# SolarPanel1.net
KiCad netlist of a schematic drawn in Altium Designer
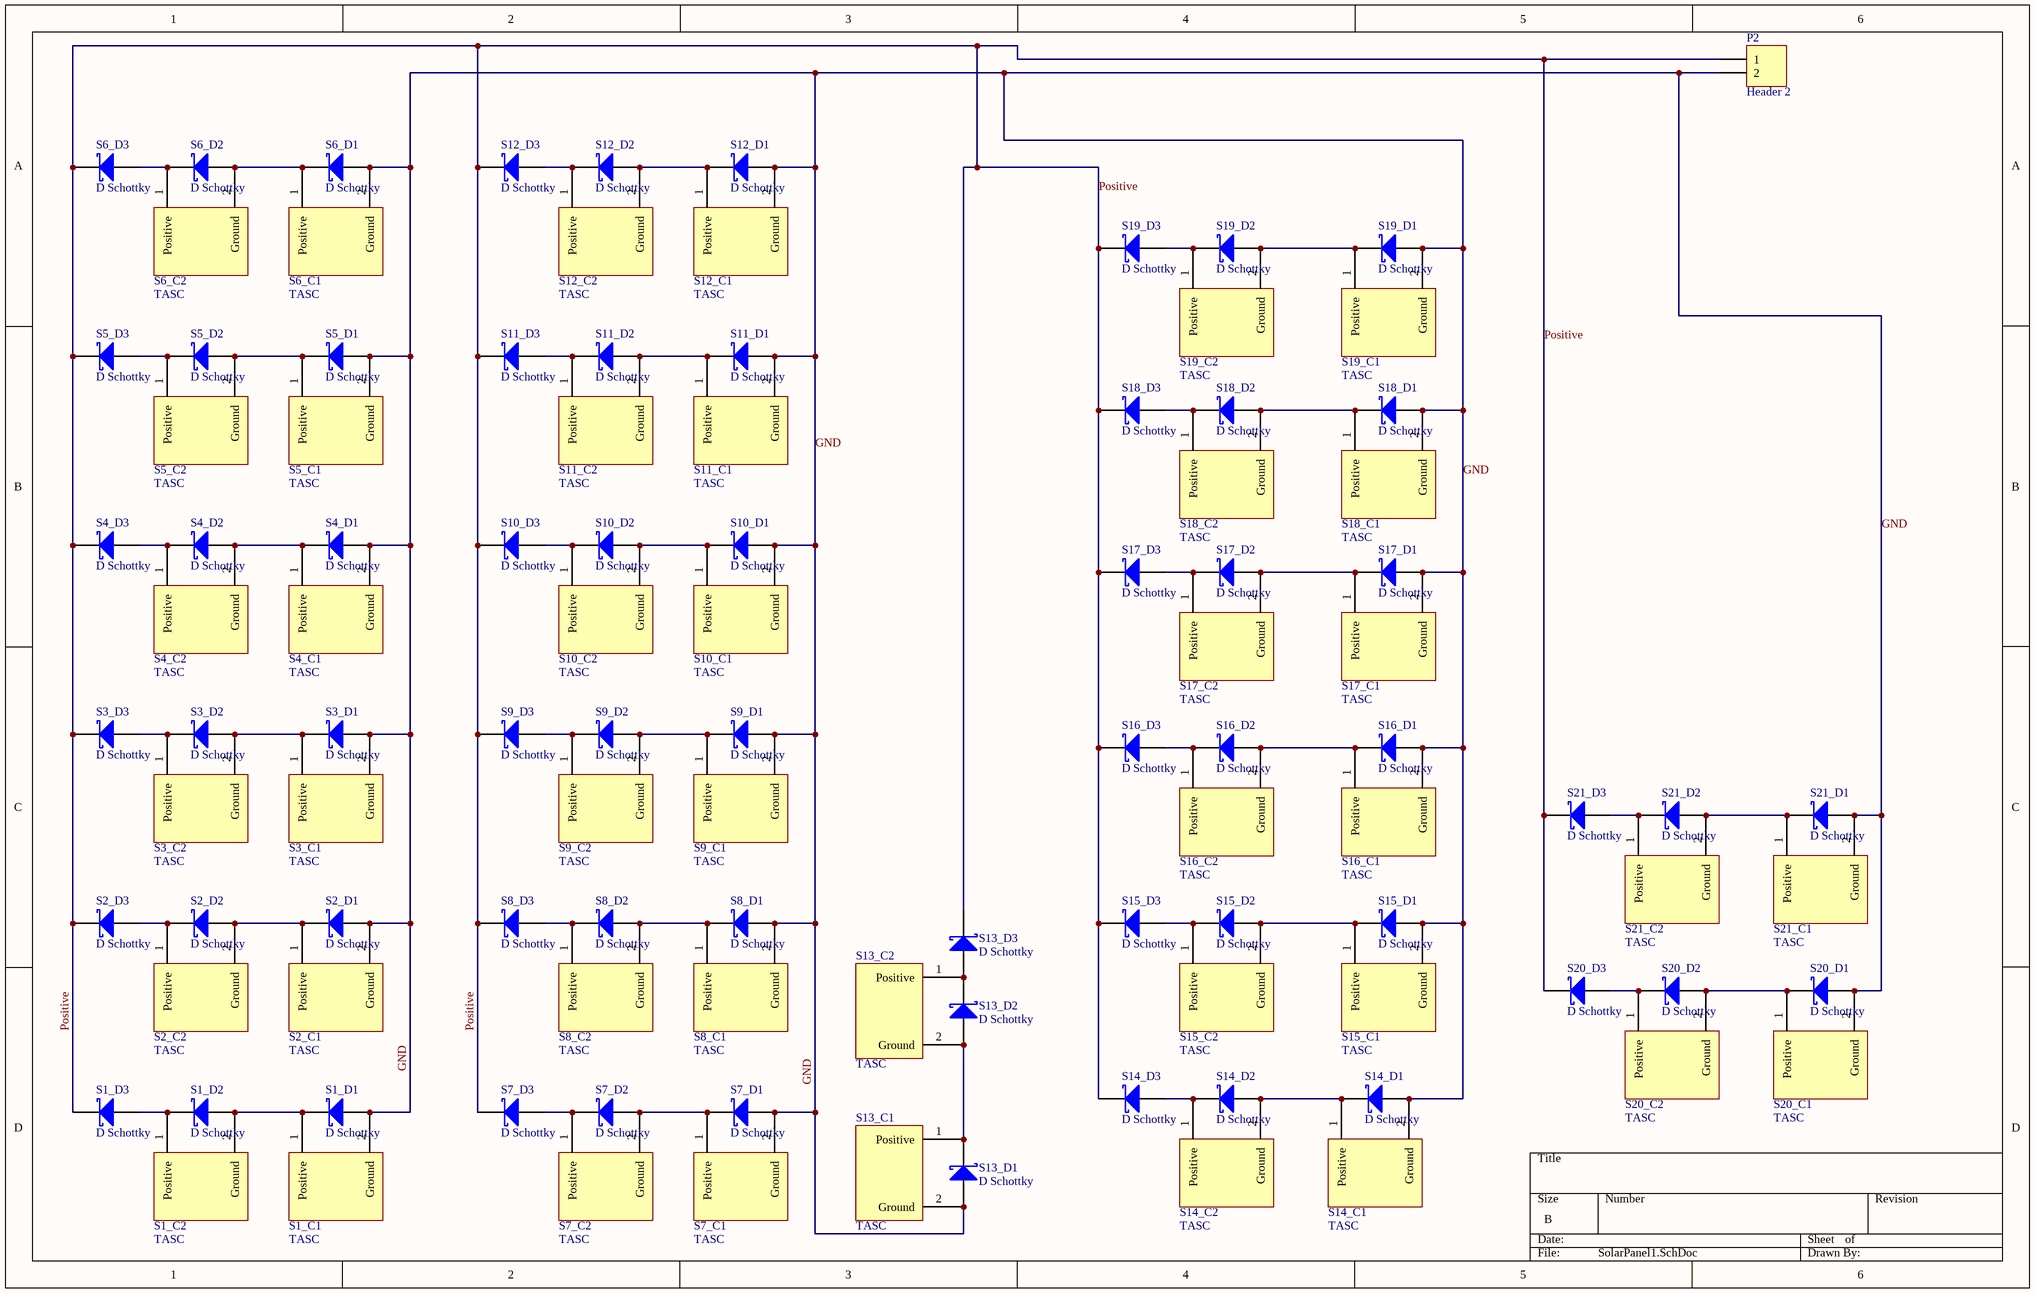
[diagram p0: SolarPanel1.SchDoc]

(export (version "E")
  (design (tool "Eeschema 10.0.6"))
  (components
    (comp (ref "P2")
      (value "Header 2")
      (footprint "HDR1X2")
      (description "Header, 2-Pin")
      (fields (field (name "PUBLISHER") "Altium Limited"))
      (libsource (lib "Miscellaneous Connectors") (part "Header 2"))
    )
    (comp (ref "S1_C1")
      (value "TASC")
      (footprint "PCBComponent_1")
      (description "TASC Solar Cell")
      (libsource (lib "SolarPanel1") (part "TASC"))
    )
    (comp (ref "S1_C2")
      (value "TASC")
      (footprint "PCBComponent_1")
      (description "TASC Solar Cell")
      (libsource (lib "SolarPanel1") (part "TASC"))
    )
    (comp (ref "S1_D1")
      (value "D Schottky")
      (footprint "SMB")
      (description "Schottky Diode")
      (fields (field (name "PUBLISHER") "Altium Limited"))
      (libsource (lib "Miscellaneous Devices") (part "D Schottky"))
    )
    (comp (ref "S1_D2")
      (value "D Schottky")
      (footprint "SMB")
      (description "Schottky Diode")
      (fields (field (name "PUBLISHER") "Altium Limited"))
      (libsource (lib "Miscellaneous Devices") (part "D Schottky"))
    )
    (comp (ref "S1_D3")
      (value "D Schottky")
      (footprint "SMB")
      (description "Schottky Diode")
      (fields (field (name "PUBLISHER") "Altium Limited"))
      (libsource (lib "Miscellaneous Devices") (part "D Schottky"))
    )
    (comp (ref "S2_C1")
      (value "TASC")
      (footprint "PCBComponent_1")
      (description "TASC Solar Cell")
      (libsource (lib "SolarPanel1") (part "TASC"))
    )
    (comp (ref "S2_C2")
      (value "TASC")
      (footprint "PCBComponent_1")
      (description "TASC Solar Cell")
      (libsource (lib "SolarPanel1") (part "TASC"))
    )
    (comp (ref "S2_D1")
      (value "D Schottky")
      (footprint "SMB")
      (description "Schottky Diode")
      (fields (field (name "PUBLISHER") "Altium Limited"))
      (libsource (lib "Miscellaneous Devices") (part "D Schottky"))
    )
    (comp (ref "S2_D2")
      (value "D Schottky")
      (footprint "SMB")
      (description "Schottky Diode")
      (fields (field (name "PUBLISHER") "Altium Limited"))
      (libsource (lib "Miscellaneous Devices") (part "D Schottky"))
    )
    (comp (ref "S2_D3")
      (value "D Schottky")
      (footprint "SMB")
      (description "Schottky Diode")
      (fields (field (name "PUBLISHER") "Altium Limited"))
      (libsource (lib "Miscellaneous Devices") (part "D Schottky"))
    )
    (comp (ref "S3_C1")
      (value "TASC")
      (footprint "PCBComponent_1")
      (description "TASC Solar Cell")
      (libsource (lib "SolarPanel1") (part "TASC"))
    )
    (comp (ref "S3_C2")
      (value "TASC")
      (footprint "PCBComponent_1")
      (description "TASC Solar Cell")
      (libsource (lib "SolarPanel1") (part "TASC"))
    )
    (comp (ref "S3_D1")
      (value "D Schottky")
      (footprint "SMB")
      (description "Schottky Diode")
      (fields (field (name "PUBLISHER") "Altium Limited"))
      (libsource (lib "Miscellaneous Devices") (part "D Schottky"))
    )
    (comp (ref "S3_D2")
      (value "D Schottky")
      (footprint "SMB")
      (description "Schottky Diode")
      (fields (field (name "PUBLISHER") "Altium Limited"))
      (libsource (lib "Miscellaneous Devices") (part "D Schottky"))
    )
    (comp (ref "S3_D3")
      (value "D Schottky")
      (footprint "SMB")
      (description "Schottky Diode")
      (fields (field (name "PUBLISHER") "Altium Limited"))
      (libsource (lib "Miscellaneous Devices") (part "D Schottky"))
    )
    (comp (ref "S4_C1")
      (value "TASC")
      (footprint "PCBComponent_1")
      (description "TASC Solar Cell")
      (libsource (lib "SolarPanel1") (part "TASC"))
    )
    (comp (ref "S4_C2")
      (value "TASC")
      (footprint "PCBComponent_1")
      (description "TASC Solar Cell")
      (libsource (lib "SolarPanel1") (part "TASC"))
    )
    (comp (ref "S4_D1")
      (value "D Schottky")
      (footprint "SMB")
      (description "Schottky Diode")
      (fields (field (name "PUBLISHER") "Altium Limited"))
      (libsource (lib "Miscellaneous Devices") (part "D Schottky"))
    )
    (comp (ref "S4_D2")
      (value "D Schottky")
      (footprint "SMB")
      (description "Schottky Diode")
      (fields (field (name "PUBLISHER") "Altium Limited"))
      (libsource (lib "Miscellaneous Devices") (part "D Schottky"))
    )
    (comp (ref "S4_D3")
      (value "D Schottky")
      (footprint "SMB")
      (description "Schottky Diode")
      (fields (field (name "PUBLISHER") "Altium Limited"))
      (libsource (lib "Miscellaneous Devices") (part "D Schottky"))
    )
    (comp (ref "S5_C1")
      (value "TASC")
      (footprint "PCBComponent_1")
      (description "TASC Solar Cell")
      (libsource (lib "SolarPanel1") (part "TASC"))
    )
    (comp (ref "S5_C2")
      (value "TASC")
      (footprint "PCBComponent_1")
      (description "TASC Solar Cell")
      (libsource (lib "SolarPanel1") (part "TASC"))
    )
    (comp (ref "S5_D1")
      (value "D Schottky")
      (footprint "SMB")
      (description "Schottky Diode")
      (fields (field (name "PUBLISHER") "Altium Limited"))
      (libsource (lib "Miscellaneous Devices") (part "D Schottky"))
    )
    (comp (ref "S5_D2")
      (value "D Schottky")
      (footprint "SMB")
      (description "Schottky Diode")
      (fields (field (name "PUBLISHER") "Altium Limited"))
      (libsource (lib "Miscellaneous Devices") (part "D Schottky"))
    )
    (comp (ref "S5_D3")
      (value "D Schottky")
      (footprint "SMB")
      (description "Schottky Diode")
      (fields (field (name "PUBLISHER") "Altium Limited"))
      (libsource (lib "Miscellaneous Devices") (part "D Schottky"))
    )
    (comp (ref "S6_C1")
      (value "TASC")
      (footprint "PCBComponent_1")
      (description "TASC Solar Cell")
      (libsource (lib "SolarPanel1") (part "TASC"))
    )
    (comp (ref "S6_C2")
      (value "TASC")
      (footprint "PCBComponent_1")
      (description "TASC Solar Cell")
      (libsource (lib "SolarPanel1") (part "TASC"))
    )
    (comp (ref "S6_D1")
      (value "D Schottky")
      (footprint "SMB")
      (description "Schottky Diode")
      (fields (field (name "PUBLISHER") "Altium Limited"))
      (libsource (lib "Miscellaneous Devices") (part "D Schottky"))
    )
    (comp (ref "S6_D2")
      (value "D Schottky")
      (footprint "SMB")
      (description "Schottky Diode")
      (fields (field (name "PUBLISHER") "Altium Limited"))
      (libsource (lib "Miscellaneous Devices") (part "D Schottky"))
    )
    (comp (ref "S6_D3")
      (value "D Schottky")
      (footprint "SMB")
      (description "Schottky Diode")
      (fields (field (name "PUBLISHER") "Altium Limited"))
      (libsource (lib "Miscellaneous Devices") (part "D Schottky"))
    )
    (comp (ref "S7_C1")
      (value "TASC")
      (footprint "PCBComponent_1")
      (description "TASC Solar Cell")
      (libsource (lib "SolarPanel1") (part "TASC"))
    )
    (comp (ref "S7_C2")
      (value "TASC")
      (footprint "PCBComponent_1")
      (description "TASC Solar Cell")
      (libsource (lib "SolarPanel1") (part "TASC"))
    )
    (comp (ref "S7_D1")
      (value "D Schottky")
      (footprint "SMB")
      (description "Schottky Diode")
      (fields (field (name "PUBLISHER") "Altium Limited"))
      (libsource (lib "Miscellaneous Devices") (part "D Schottky"))
    )
    (comp (ref "S7_D2")
      (value "D Schottky")
      (footprint "SMB")
      (description "Schottky Diode")
      (fields (field (name "PUBLISHER") "Altium Limited"))
      (libsource (lib "Miscellaneous Devices") (part "D Schottky"))
    )
    (comp (ref "S7_D3")
      (value "D Schottky")
      (footprint "SMB")
      (description "Schottky Diode")
      (fields (field (name "PUBLISHER") "Altium Limited"))
      (libsource (lib "Miscellaneous Devices") (part "D Schottky"))
    )
    (comp (ref "S8_C1")
      (value "TASC")
      (footprint "PCBComponent_1")
      (description "TASC Solar Cell")
      (libsource (lib "SolarPanel1") (part "TASC"))
    )
    (comp (ref "S8_C2")
      (value "TASC")
      (footprint "PCBComponent_1")
      (description "TASC Solar Cell")
      (libsource (lib "SolarPanel1") (part "TASC"))
    )
    (comp (ref "S8_D1")
      (value "D Schottky")
      (footprint "SMB")
      (description "Schottky Diode")
      (fields (field (name "PUBLISHER") "Altium Limited"))
      (libsource (lib "Miscellaneous Devices") (part "D Schottky"))
    )
    (comp (ref "S8_D2")
      (value "D Schottky")
      (footprint "SMB")
      (description "Schottky Diode")
      (fields (field (name "PUBLISHER") "Altium Limited"))
      (libsource (lib "Miscellaneous Devices") (part "D Schottky"))
    )
    (comp (ref "S8_D3")
      (value "D Schottky")
      (footprint "SMB")
      (description "Schottky Diode")
      (fields (field (name "PUBLISHER") "Altium Limited"))
      (libsource (lib "Miscellaneous Devices") (part "D Schottky"))
    )
    (comp (ref "S9_C1")
      (value "TASC")
      (footprint "PCBComponent_1")
      (description "TASC Solar Cell")
      (libsource (lib "SolarPanel1") (part "TASC"))
    )
    (comp (ref "S9_C2")
      (value "TASC")
      (footprint "PCBComponent_1")
      (description "TASC Solar Cell")
      (libsource (lib "SolarPanel1") (part "TASC"))
    )
    (comp (ref "S9_D1")
      (value "D Schottky")
      (footprint "SMB")
      (description "Schottky Diode")
      (fields (field (name "PUBLISHER") "Altium Limited"))
      (libsource (lib "Miscellaneous Devices") (part "D Schottky"))
    )
    (comp (ref "S9_D2")
      (value "D Schottky")
      (footprint "SMB")
      (description "Schottky Diode")
      (fields (field (name "PUBLISHER") "Altium Limited"))
      (libsource (lib "Miscellaneous Devices") (part "D Schottky"))
    )
    (comp (ref "S9_D3")
      (value "D Schottky")
      (footprint "SMB")
      (description "Schottky Diode")
      (fields (field (name "PUBLISHER") "Altium Limited"))
      (libsource (lib "Miscellaneous Devices") (part "D Schottky"))
    )
    (comp (ref "S10_C1")
      (value "TASC")
      (footprint "PCBComponent_1")
      (description "TASC Solar Cell")
      (libsource (lib "SolarPanel1") (part "TASC"))
    )
    (comp (ref "S10_C2")
      (value "TASC")
      (footprint "PCBComponent_1")
      (description "TASC Solar Cell")
      (libsource (lib "SolarPanel1") (part "TASC"))
    )
    (comp (ref "S10_D1")
      (value "D Schottky")
      (footprint "SMB")
      (description "Schottky Diode")
      (fields (field (name "PUBLISHER") "Altium Limited"))
      (libsource (lib "Miscellaneous Devices") (part "D Schottky"))
    )
    (comp (ref "S10_D2")
      (value "D Schottky")
      (footprint "SMB")
      (description "Schottky Diode")
      (fields (field (name "PUBLISHER") "Altium Limited"))
      (libsource (lib "Miscellaneous Devices") (part "D Schottky"))
    )
    (comp (ref "S10_D3")
      (value "D Schottky")
      (footprint "SMB")
      (description "Schottky Diode")
      (fields (field (name "PUBLISHER") "Altium Limited"))
      (libsource (lib "Miscellaneous Devices") (part "D Schottky"))
    )
    (comp (ref "S11_C1")
      (value "TASC")
      (footprint "PCBComponent_1")
      (description "TASC Solar Cell")
      (libsource (lib "SolarPanel1") (part "TASC"))
    )
    (comp (ref "S11_C2")
      (value "TASC")
      (footprint "PCBComponent_1")
      (description "TASC Solar Cell")
      (libsource (lib "SolarPanel1") (part "TASC"))
    )
    (comp (ref "S11_D1")
      (value "D Schottky")
      (footprint "SMB")
      (description "Schottky Diode")
      (fields (field (name "PUBLISHER") "Altium Limited"))
      (libsource (lib "Miscellaneous Devices") (part "D Schottky"))
    )
    (comp (ref "S11_D2")
      (value "D Schottky")
      (footprint "SMB")
      (description "Schottky Diode")
      (fields (field (name "PUBLISHER") "Altium Limited"))
      (libsource (lib "Miscellaneous Devices") (part "D Schottky"))
    )
    (comp (ref "S11_D3")
      (value "D Schottky")
      (footprint "SMB")
      (description "Schottky Diode")
      (fields (field (name "PUBLISHER") "Altium Limited"))
      (libsource (lib "Miscellaneous Devices") (part "D Schottky"))
    )
    (comp (ref "S12_C1")
      (value "TASC")
      (footprint "PCBComponent_1")
      (description "TASC Solar Cell")
      (libsource (lib "SolarPanel1") (part "TASC"))
    )
    (comp (ref "S12_C2")
      (value "TASC")
      (footprint "PCBComponent_1")
      (description "TASC Solar Cell")
      (libsource (lib "SolarPanel1") (part "TASC"))
    )
    (comp (ref "S12_D1")
      (value "D Schottky")
      (footprint "SMB")
      (description "Schottky Diode")
      (fields (field (name "PUBLISHER") "Altium Limited"))
      (libsource (lib "Miscellaneous Devices") (part "D Schottky"))
    )
    (comp (ref "S12_D2")
      (value "D Schottky")
      (footprint "SMB")
      (description "Schottky Diode")
      (fields (field (name "PUBLISHER") "Altium Limited"))
      (libsource (lib "Miscellaneous Devices") (part "D Schottky"))
    )
    (comp (ref "S12_D3")
      (value "D Schottky")
      (footprint "SMB")
      (description "Schottky Diode")
      (fields (field (name "PUBLISHER") "Altium Limited"))
      (libsource (lib "Miscellaneous Devices") (part "D Schottky"))
    )
    (comp (ref "S13_C1")
      (value "TASC")
      (footprint "PCBComponent_1")
      (description "TASC Solar Cell")
      (libsource (lib "") (part "TASC_1"))
    )
    (comp (ref "S13_C2")
      (value "TASC")
      (footprint "PCBComponent_1")
      (description "TASC Solar Cell")
      (libsource (lib "") (part "TASC_1"))
    )
    (comp (ref "S13_D1")
      (value "D Schottky")
      (footprint "SMB")
      (description "Schottky Diode")
      (fields (field (name "PUBLISHER") "Altium Limited"))
      (libsource (lib "Miscellaneous Devices") (part "D Schottky"))
    )
    (comp (ref "S13_D2")
      (value "D Schottky")
      (footprint "SMB")
      (description "Schottky Diode")
      (fields (field (name "PUBLISHER") "Altium Limited"))
      (libsource (lib "Miscellaneous Devices") (part "D Schottky"))
    )
    (comp (ref "S13_D3")
      (value "D Schottky")
      (footprint "SMB")
      (description "Schottky Diode")
      (fields (field (name "PUBLISHER") "Altium Limited"))
      (libsource (lib "Miscellaneous Devices") (part "D Schottky"))
    )
    (comp (ref "S14_C1")
      (value "TASC")
      (footprint "PCBComponent_1")
      (description "TASC Solar Cell")
      (libsource (lib "SolarPanel1") (part "TASC"))
    )
    (comp (ref "S14_C2")
      (value "TASC")
      (footprint "PCBComponent_1")
      (description "TASC Solar Cell")
      (libsource (lib "SolarPanel1") (part "TASC"))
    )
    (comp (ref "S14_D1")
      (value "D Schottky")
      (footprint "SMB")
      (description "Schottky Diode")
      (fields (field (name "PUBLISHER") "Altium Limited"))
      (libsource (lib "Miscellaneous Devices") (part "D Schottky"))
    )
    (comp (ref "S14_D2")
      (value "D Schottky")
      (footprint "SMB")
      (description "Schottky Diode")
      (fields (field (name "PUBLISHER") "Altium Limited"))
      (libsource (lib "Miscellaneous Devices") (part "D Schottky"))
    )
    (comp (ref "S14_D3")
      (value "D Schottky")
      (footprint "SMB")
      (description "Schottky Diode")
      (fields (field (name "PUBLISHER") "Altium Limited"))
      (libsource (lib "Miscellaneous Devices") (part "D Schottky"))
    )
    (comp (ref "S15_C1")
      (value "TASC")
      (footprint "PCBComponent_1")
      (description "TASC Solar Cell")
      (libsource (lib "SolarPanel1") (part "TASC"))
    )
    (comp (ref "S15_C2")
      (value "TASC")
      (footprint "PCBComponent_1")
      (description "TASC Solar Cell")
      (libsource (lib "SolarPanel1") (part "TASC"))
    )
    (comp (ref "S15_D1")
      (value "D Schottky")
      (footprint "SMB")
      (description "Schottky Diode")
      (fields (field (name "PUBLISHER") "Altium Limited"))
      (libsource (lib "Miscellaneous Devices") (part "D Schottky"))
    )
    (comp (ref "S15_D2")
      (value "D Schottky")
      (footprint "SMB")
      (description "Schottky Diode")
      (fields (field (name "PUBLISHER") "Altium Limited"))
      (libsource (lib "Miscellaneous Devices") (part "D Schottky"))
    )
    (comp (ref "S15_D3")
      (value "D Schottky")
      (footprint "SMB")
      (description "Schottky Diode")
      (fields (field (name "PUBLISHER") "Altium Limited"))
      (libsource (lib "Miscellaneous Devices") (part "D Schottky"))
    )
    (comp (ref "S16_C1")
      (value "TASC")
      (footprint "PCBComponent_1")
      (description "TASC Solar Cell")
      (libsource (lib "SolarPanel1") (part "TASC"))
    )
    (comp (ref "S16_C2")
      (value "TASC")
      (footprint "PCBComponent_1")
      (description "TASC Solar Cell")
      (libsource (lib "SolarPanel1") (part "TASC"))
    )
    (comp (ref "S16_D1")
      (value "D Schottky")
      (footprint "SMB")
      (description "Schottky Diode")
      (fields (field (name "PUBLISHER") "Altium Limited"))
      (libsource (lib "Miscellaneous Devices") (part "D Schottky"))
    )
    (comp (ref "S16_D2")
      (value "D Schottky")
      (footprint "SMB")
      (description "Schottky Diode")
      (fields (field (name "PUBLISHER") "Altium Limited"))
      (libsource (lib "Miscellaneous Devices") (part "D Schottky"))
    )
    (comp (ref "S16_D3")
      (value "D Schottky")
      (footprint "SMB")
      (description "Schottky Diode")
      (fields (field (name "PUBLISHER") "Altium Limited"))
      (libsource (lib "Miscellaneous Devices") (part "D Schottky"))
    )
    (comp (ref "S17_C1")
      (value "TASC")
      (footprint "PCBComponent_1")
      (description "TASC Solar Cell")
      (libsource (lib "SolarPanel1") (part "TASC"))
    )
    (comp (ref "S17_C2")
      (value "TASC")
      (footprint "PCBComponent_1")
      (description "TASC Solar Cell")
      (libsource (lib "SolarPanel1") (part "TASC"))
    )
    (comp (ref "S17_D1")
      (value "D Schottky")
      (footprint "SMB")
      (description "Schottky Diode")
      (fields (field (name "PUBLISHER") "Altium Limited"))
      (libsource (lib "Miscellaneous Devices") (part "D Schottky"))
    )
    (comp (ref "S17_D2")
      (value "D Schottky")
      (footprint "SMB")
      (description "Schottky Diode")
      (fields (field (name "PUBLISHER") "Altium Limited"))
      (libsource (lib "Miscellaneous Devices") (part "D Schottky"))
    )
    (comp (ref "S17_D3")
      (value "D Schottky")
      (footprint "SMB")
      (description "Schottky Diode")
      (fields (field (name "PUBLISHER") "Altium Limited"))
      (libsource (lib "Miscellaneous Devices") (part "D Schottky"))
    )
    (comp (ref "S18_C1")
      (value "TASC")
      (footprint "PCBComponent_1")
      (description "TASC Solar Cell")
      (libsource (lib "SolarPanel1") (part "TASC"))
    )
    (comp (ref "S18_C2")
      (value "TASC")
      (footprint "PCBComponent_1")
      (description "TASC Solar Cell")
      (libsource (lib "SolarPanel1") (part "TASC"))
    )
    (comp (ref "S18_D1")
      (value "D Schottky")
      (footprint "SMB")
      (description "Schottky Diode")
      (fields (field (name "PUBLISHER") "Altium Limited"))
      (libsource (lib "Miscellaneous Devices") (part "D Schottky"))
    )
    (comp (ref "S18_D2")
      (value "D Schottky")
      (footprint "SMB")
      (description "Schottky Diode")
      (fields (field (name "PUBLISHER") "Altium Limited"))
      (libsource (lib "Miscellaneous Devices") (part "D Schottky"))
    )
    (comp (ref "S18_D3")
      (value "D Schottky")
      (footprint "SMB")
      (description "Schottky Diode")
      (fields (field (name "PUBLISHER") "Altium Limited"))
      (libsource (lib "Miscellaneous Devices") (part "D Schottky"))
    )
    (comp (ref "S19_C1")
      (value "TASC")
      (footprint "PCBComponent_1")
      (description "TASC Solar Cell")
      (libsource (lib "SolarPanel1") (part "TASC"))
    )
    (comp (ref "S19_C2")
      (value "TASC")
      (footprint "PCBComponent_1")
      (description "TASC Solar Cell")
      (libsource (lib "SolarPanel1") (part "TASC"))
    )
    (comp (ref "S19_D1")
      (value "D Schottky")
      (footprint "SMB")
      (description "Schottky Diode")
      (fields (field (name "PUBLISHER") "Altium Limited"))
      (libsource (lib "Miscellaneous Devices") (part "D Schottky"))
    )
    (comp (ref "S19_D2")
      (value "D Schottky")
      (footprint "SMB")
      (description "Schottky Diode")
      (fields (field (name "PUBLISHER") "Altium Limited"))
      (libsource (lib "Miscellaneous Devices") (part "D Schottky"))
    )
    (comp (ref "S19_D3")
      (value "D Schottky")
      (footprint "SMB")
      (description "Schottky Diode")
      (fields (field (name "PUBLISHER") "Altium Limited"))
      (libsource (lib "Miscellaneous Devices") (part "D Schottky"))
    )
    (comp (ref "S20_C1")
      (value "TASC")
      (footprint "PCBComponent_1")
      (description "TASC Solar Cell")
      (libsource (lib "SolarPanel1") (part "TASC"))
    )
    (comp (ref "S20_C2")
      (value "TASC")
      (footprint "PCBComponent_1")
      (description "TASC Solar Cell")
      (libsource (lib "SolarPanel1") (part "TASC"))
    )
    (comp (ref "S20_D1")
      (value "D Schottky")
      (footprint "SMB")
      (description "Schottky Diode")
      (fields (field (name "PUBLISHER") "Altium Limited"))
      (libsource (lib "Miscellaneous Devices") (part "D Schottky"))
    )
    (comp (ref "S20_D2")
      (value "D Schottky")
      (footprint "SMB")
      (description "Schottky Diode")
      (fields (field (name "PUBLISHER") "Altium Limited"))
      (libsource (lib "Miscellaneous Devices") (part "D Schottky"))
    )
    (comp (ref "S20_D3")
      (value "D Schottky")
      (footprint "SMB")
      (description "Schottky Diode")
      (fields (field (name "PUBLISHER") "Altium Limited"))
      (libsource (lib "Miscellaneous Devices") (part "D Schottky"))
    )
    (comp (ref "S21_C1")
      (value "TASC")
      (footprint "PCBComponent_1")
      (description "TASC Solar Cell")
      (libsource (lib "SolarPanel1") (part "TASC"))
    )
    (comp (ref "S21_C2")
      (value "TASC")
      (footprint "PCBComponent_1")
      (description "TASC Solar Cell")
      (libsource (lib "SolarPanel1") (part "TASC"))
    )
    (comp (ref "S21_D1")
      (value "D Schottky")
      (footprint "SMB")
      (description "Schottky Diode")
      (fields (field (name "PUBLISHER") "Altium Limited"))
      (libsource (lib "Miscellaneous Devices") (part "D Schottky"))
    )
    (comp (ref "S21_D2")
      (value "D Schottky")
      (footprint "SMB")
      (description "Schottky Diode")
      (fields (field (name "PUBLISHER") "Altium Limited"))
      (libsource (lib "Miscellaneous Devices") (part "D Schottky"))
    )
    (comp (ref "S21_D3")
      (value "D Schottky")
      (footprint "SMB")
      (description "Schottky Diode")
      (fields (field (name "PUBLISHER") "Altium Limited"))
      (libsource (lib "Miscellaneous Devices") (part "D Schottky"))
    )
  )
  (nets
    (net (code "1") (name "/GND") (class "Default")
      (node (ref "P2") (pin "2") (pinfunction "2_2") (pintype "passive"))
      (node (ref "S10_C1") (pin "2") (pinfunction "Ground_2") (pintype "power_in"))
      (node (ref "S10_D1") (pin "1") (pinfunction "A_1") (pintype "passive"))
      (node (ref "S11_C1") (pin "2") (pinfunction "Ground_2") (pintype "power_in"))
      (node (ref "S11_D1") (pin "1") (pinfunction "A_1") (pintype "passive"))
      (node (ref "S12_C1") (pin "2") (pinfunction "Ground_2") (pintype "power_in"))
      (node (ref "S12_D1") (pin "1") (pinfunction "A_1") (pintype "passive"))
      (node (ref "S13_C1") (pin "2") (pinfunction "Ground_2") (pintype "power_in"))
      (node (ref "S13_D1") (pin "1") (pinfunction "A_1") (pintype "passive"))
      (node (ref "S14_C1") (pin "2") (pinfunction "Ground_2") (pintype "power_in"))
      (node (ref "S14_D1") (pin "1") (pinfunction "A_1") (pintype "passive"))
      (node (ref "S15_C1") (pin "2") (pinfunction "Ground_2") (pintype "power_in"))
      (node (ref "S15_D1") (pin "1") (pinfunction "A_1") (pintype "passive"))
      (node (ref "S16_C1") (pin "2") (pinfunction "Ground_2") (pintype "power_in"))
      (node (ref "S16_D1") (pin "1") (pinfunction "A_1") (pintype "passive"))
      (node (ref "S17_C1") (pin "2") (pinfunction "Ground_2") (pintype "power_in"))
      (node (ref "S17_D1") (pin "1") (pinfunction "A_1") (pintype "passive"))
      (node (ref "S18_C1") (pin "2") (pinfunction "Ground_2") (pintype "power_in"))
      (node (ref "S18_D1") (pin "1") (pinfunction "A_1") (pintype "passive"))
      (node (ref "S19_C1") (pin "2") (pinfunction "Ground_2") (pintype "power_in"))
      (node (ref "S19_D1") (pin "1") (pinfunction "A_1") (pintype "passive"))
      (node (ref "S1_C1") (pin "2") (pinfunction "Ground_2") (pintype "power_in"))
      (node (ref "S1_D1") (pin "1") (pinfunction "A_1") (pintype "passive"))
      (node (ref "S20_C1") (pin "2") (pinfunction "Ground_2") (pintype "power_in"))
      (node (ref "S20_D1") (pin "1") (pinfunction "A_1") (pintype "passive"))
      (node (ref "S21_C1") (pin "2") (pinfunction "Ground_2") (pintype "power_in"))
      (node (ref "S21_D1") (pin "1") (pinfunction "A_1") (pintype "passive"))
      (node (ref "S2_C1") (pin "2") (pinfunction "Ground_2") (pintype "power_in"))
      (node (ref "S2_D1") (pin "1") (pinfunction "A_1") (pintype "passive"))
      (node (ref "S3_C1") (pin "2") (pinfunction "Ground_2") (pintype "power_in"))
      (node (ref "S3_D1") (pin "1") (pinfunction "A_1") (pintype "passive"))
      (node (ref "S4_C1") (pin "2") (pinfunction "Ground_2") (pintype "power_in"))
      (node (ref "S4_D1") (pin "1") (pinfunction "A_1") (pintype "passive"))
      (node (ref "S5_C1") (pin "2") (pinfunction "Ground_2") (pintype "power_in"))
      (node (ref "S5_D1") (pin "1") (pinfunction "A_1") (pintype "passive"))
      (node (ref "S6_C1") (pin "2") (pinfunction "Ground_2") (pintype "power_in"))
      (node (ref "S6_D1") (pin "1") (pinfunction "A_1") (pintype "passive"))
      (node (ref "S7_C1") (pin "2") (pinfunction "Ground_2") (pintype "power_in"))
      (node (ref "S7_D1") (pin "1") (pinfunction "A_1") (pintype "passive"))
      (node (ref "S8_C1") (pin "2") (pinfunction "Ground_2") (pintype "power_in"))
      (node (ref "S8_D1") (pin "1") (pinfunction "A_1") (pintype "passive"))
      (node (ref "S9_C1") (pin "2") (pinfunction "Ground_2") (pintype "power_in"))
      (node (ref "S9_D1") (pin "1") (pinfunction "A_1") (pintype "passive"))
    )
    (net (code "2") (name "/Positive") (class "Default")
      (node (ref "P2") (pin "1") (pinfunction "1_1") (pintype "passive"))
      (node (ref "S10_D3") (pin "2") (pinfunction "K_2") (pintype "passive"))
      (node (ref "S11_D3") (pin "2") (pinfunction "K_2") (pintype "passive"))
      (node (ref "S12_D3") (pin "2") (pinfunction "K_2") (pintype "passive"))
      (node (ref "S13_D3") (pin "2") (pinfunction "K_2") (pintype "passive"))
      (node (ref "S14_D3") (pin "2") (pinfunction "K_2") (pintype "passive"))
      (node (ref "S15_D3") (pin "2") (pinfunction "K_2") (pintype "passive"))
      (node (ref "S16_D3") (pin "2") (pinfunction "K_2") (pintype "passive"))
      (node (ref "S17_D3") (pin "2") (pinfunction "K_2") (pintype "passive"))
      (node (ref "S18_D3") (pin "2") (pinfunction "K_2") (pintype "passive"))
      (node (ref "S19_D3") (pin "2") (pinfunction "K_2") (pintype "passive"))
      (node (ref "S1_D3") (pin "2") (pinfunction "K_2") (pintype "passive"))
      (node (ref "S20_D3") (pin "2") (pinfunction "K_2") (pintype "passive"))
      (node (ref "S21_D3") (pin "2") (pinfunction "K_2") (pintype "passive"))
      (node (ref "S2_D3") (pin "2") (pinfunction "K_2") (pintype "passive"))
      (node (ref "S3_D3") (pin "2") (pinfunction "K_2") (pintype "passive"))
      (node (ref "S4_D3") (pin "2") (pinfunction "K_2") (pintype "passive"))
      (node (ref "S5_D3") (pin "2") (pinfunction "K_2") (pintype "passive"))
      (node (ref "S6_D3") (pin "2") (pinfunction "K_2") (pintype "passive"))
      (node (ref "S7_D3") (pin "2") (pinfunction "K_2") (pintype "passive"))
      (node (ref "S8_D3") (pin "2") (pinfunction "K_2") (pintype "passive"))
      (node (ref "S9_D3") (pin "2") (pinfunction "K_2") (pintype "passive"))
    )
    (net (code "3") (name "Net-(S1_C1-Positive)") (class "Default")
      (node (ref "S1_C1") (pin "1") (pinfunction "Positive_1") (pintype "power_in"))
      (node (ref "S1_C2") (pin "2") (pinfunction "Ground_2") (pintype "power_in"))
      (node (ref "S1_D1") (pin "2") (pinfunction "K_2") (pintype "passive"))
      (node (ref "S1_D2") (pin "1") (pinfunction "A_1") (pintype "passive"))
    )
    (net (code "4") (name "Net-(S1_C2-Positive)") (class "Default")
      (node (ref "S1_C2") (pin "1") (pinfunction "Positive_1") (pintype "power_in"))
      (node (ref "S1_D2") (pin "2") (pinfunction "K_2") (pintype "passive"))
      (node (ref "S1_D3") (pin "1") (pinfunction "A_1") (pintype "passive"))
    )
    (net (code "5") (name "Net-(S2_C1-Positive)") (class "Default")
      (node (ref "S2_C1") (pin "1") (pinfunction "Positive_1") (pintype "power_in"))
      (node (ref "S2_C2") (pin "2") (pinfunction "Ground_2") (pintype "power_in"))
      (node (ref "S2_D1") (pin "2") (pinfunction "K_2") (pintype "passive"))
      (node (ref "S2_D2") (pin "1") (pinfunction "A_1") (pintype "passive"))
    )
    (net (code "6") (name "Net-(S2_C2-Positive)") (class "Default")
      (node (ref "S2_C2") (pin "1") (pinfunction "Positive_1") (pintype "power_in"))
      (node (ref "S2_D2") (pin "2") (pinfunction "K_2") (pintype "passive"))
      (node (ref "S2_D3") (pin "1") (pinfunction "A_1") (pintype "passive"))
    )
    (net (code "7") (name "Net-(S3_C1-Positive)") (class "Default")
      (node (ref "S3_C1") (pin "1") (pinfunction "Positive_1") (pintype "power_in"))
      (node (ref "S3_C2") (pin "2") (pinfunction "Ground_2") (pintype "power_in"))
      (node (ref "S3_D1") (pin "2") (pinfunction "K_2") (pintype "passive"))
      (node (ref "S3_D2") (pin "1") (pinfunction "A_1") (pintype "passive"))
    )
    (net (code "8") (name "Net-(S3_C2-Positive)") (class "Default")
      (node (ref "S3_C2") (pin "1") (pinfunction "Positive_1") (pintype "power_in"))
      (node (ref "S3_D2") (pin "2") (pinfunction "K_2") (pintype "passive"))
      (node (ref "S3_D3") (pin "1") (pinfunction "A_1") (pintype "passive"))
    )
    (net (code "9") (name "Net-(S4_C1-Positive)") (class "Default")
      (node (ref "S4_C1") (pin "1") (pinfunction "Positive_1") (pintype "power_in"))
      (node (ref "S4_C2") (pin "2") (pinfunction "Ground_2") (pintype "power_in"))
      (node (ref "S4_D1") (pin "2") (pinfunction "K_2") (pintype "passive"))
      (node (ref "S4_D2") (pin "1") (pinfunction "A_1") (pintype "passive"))
    )
    (net (code "10") (name "Net-(S4_C2-Positive)") (class "Default")
      (node (ref "S4_C2") (pin "1") (pinfunction "Positive_1") (pintype "power_in"))
      (node (ref "S4_D2") (pin "2") (pinfunction "K_2") (pintype "passive"))
      (node (ref "S4_D3") (pin "1") (pinfunction "A_1") (pintype "passive"))
    )
    (net (code "11") (name "Net-(S5_C1-Positive)") (class "Default")
      (node (ref "S5_C1") (pin "1") (pinfunction "Positive_1") (pintype "power_in"))
      (node (ref "S5_C2") (pin "2") (pinfunction "Ground_2") (pintype "power_in"))
      (node (ref "S5_D1") (pin "2") (pinfunction "K_2") (pintype "passive"))
      (node (ref "S5_D2") (pin "1") (pinfunction "A_1") (pintype "passive"))
    )
    (net (code "12") (name "Net-(S5_C2-Positive)") (class "Default")
      (node (ref "S5_C2") (pin "1") (pinfunction "Positive_1") (pintype "power_in"))
      (node (ref "S5_D2") (pin "2") (pinfunction "K_2") (pintype "passive"))
      (node (ref "S5_D3") (pin "1") (pinfunction "A_1") (pintype "passive"))
    )
    (net (code "13") (name "Net-(S6_C1-Positive)") (class "Default")
      (node (ref "S6_C1") (pin "1") (pinfunction "Positive_1") (pintype "power_in"))
      (node (ref "S6_C2") (pin "2") (pinfunction "Ground_2") (pintype "power_in"))
      (node (ref "S6_D1") (pin "2") (pinfunction "K_2") (pintype "passive"))
      (node (ref "S6_D2") (pin "1") (pinfunction "A_1") (pintype "passive"))
    )
    (net (code "14") (name "Net-(S6_C2-Positive)") (class "Default")
      (node (ref "S6_C2") (pin "1") (pinfunction "Positive_1") (pintype "power_in"))
      (node (ref "S6_D2") (pin "2") (pinfunction "K_2") (pintype "passive"))
      (node (ref "S6_D3") (pin "1") (pinfunction "A_1") (pintype "passive"))
    )
    (net (code "15") (name "Net-(S7_C1-Positive)") (class "Default")
      (node (ref "S7_C1") (pin "1") (pinfunction "Positive_1") (pintype "power_in"))
      (node (ref "S7_C2") (pin "2") (pinfunction "Ground_2") (pintype "power_in"))
      (node (ref "S7_D1") (pin "2") (pinfunction "K_2") (pintype "passive"))
      (node (ref "S7_D2") (pin "1") (pinfunction "A_1") (pintype "passive"))
    )
    (net (code "16") (name "Net-(S7_C2-Positive)") (class "Default")
      (node (ref "S7_C2") (pin "1") (pinfunction "Positive_1") (pintype "power_in"))
      (node (ref "S7_D2") (pin "2") (pinfunction "K_2") (pintype "passive"))
      (node (ref "S7_D3") (pin "1") (pinfunction "A_1") (pintype "passive"))
    )
    (net (code "17") (name "Net-(S8_C1-Positive)") (class "Default")
      (node (ref "S8_C1") (pin "1") (pinfunction "Positive_1") (pintype "power_in"))
      (node (ref "S8_C2") (pin "2") (pinfunction "Ground_2") (pintype "power_in"))
      (node (ref "S8_D1") (pin "2") (pinfunction "K_2") (pintype "passive"))
      (node (ref "S8_D2") (pin "1") (pinfunction "A_1") (pintype "passive"))
    )
    (net (code "18") (name "Net-(S8_C2-Positive)") (class "Default")
      (node (ref "S8_C2") (pin "1") (pinfunction "Positive_1") (pintype "power_in"))
      (node (ref "S8_D2") (pin "2") (pinfunction "K_2") (pintype "passive"))
      (node (ref "S8_D3") (pin "1") (pinfunction "A_1") (pintype "passive"))
    )
    (net (code "19") (name "Net-(S9_C1-Positive)") (class "Default")
      (node (ref "S9_C1") (pin "1") (pinfunction "Positive_1") (pintype "power_in"))
      (node (ref "S9_C2") (pin "2") (pinfunction "Ground_2") (pintype "power_in"))
      (node (ref "S9_D1") (pin "2") (pinfunction "K_2") (pintype "passive"))
      (node (ref "S9_D2") (pin "1") (pinfunction "A_1") (pintype "passive"))
    )
    (net (code "20") (name "Net-(S9_C2-Positive)") (class "Default")
      (node (ref "S9_C2") (pin "1") (pinfunction "Positive_1") (pintype "power_in"))
      (node (ref "S9_D2") (pin "2") (pinfunction "K_2") (pintype "passive"))
      (node (ref "S9_D3") (pin "1") (pinfunction "A_1") (pintype "passive"))
    )
    (net (code "21") (name "Net-(S10_C1-Positive)") (class "Default")
      (node (ref "S10_C1") (pin "1") (pinfunction "Positive_1") (pintype "power_in"))
      (node (ref "S10_C2") (pin "2") (pinfunction "Ground_2") (pintype "power_in"))
      (node (ref "S10_D1") (pin "2") (pinfunction "K_2") (pintype "passive"))
      (node (ref "S10_D2") (pin "1") (pinfunction "A_1") (pintype "passive"))
    )
    (net (code "22") (name "Net-(S10_C2-Positive)") (class "Default")
      (node (ref "S10_C2") (pin "1") (pinfunction "Positive_1") (pintype "power_in"))
      (node (ref "S10_D2") (pin "2") (pinfunction "K_2") (pintype "passive"))
      (node (ref "S10_D3") (pin "1") (pinfunction "A_1") (pintype "passive"))
    )
    (net (code "23") (name "Net-(S11_C1-Positive)") (class "Default")
      (node (ref "S11_C1") (pin "1") (pinfunction "Positive_1") (pintype "power_in"))
      (node (ref "S11_C2") (pin "2") (pinfunction "Ground_2") (pintype "power_in"))
      (node (ref "S11_D1") (pin "2") (pinfunction "K_2") (pintype "passive"))
      (node (ref "S11_D2") (pin "1") (pinfunction "A_1") (pintype "passive"))
    )
    (net (code "24") (name "Net-(S11_C2-Positive)") (class "Default")
      (node (ref "S11_C2") (pin "1") (pinfunction "Positive_1") (pintype "power_in"))
      (node (ref "S11_D2") (pin "2") (pinfunction "K_2") (pintype "passive"))
      (node (ref "S11_D3") (pin "1") (pinfunction "A_1") (pintype "passive"))
    )
    (net (code "25") (name "Net-(S12_C1-Positive)") (class "Default")
      (node (ref "S12_C1") (pin "1") (pinfunction "Positive_1") (pintype "power_in"))
      (node (ref "S12_C2") (pin "2") (pinfunction "Ground_2") (pintype "power_in"))
      (node (ref "S12_D1") (pin "2") (pinfunction "K_2") (pintype "passive"))
      (node (ref "S12_D2") (pin "1") (pinfunction "A_1") (pintype "passive"))
    )
    (net (code "26") (name "Net-(S12_C2-Positive)") (class "Default")
      (node (ref "S12_C2") (pin "1") (pinfunction "Positive_1") (pintype "power_in"))
      (node (ref "S12_D2") (pin "2") (pinfunction "K_2") (pintype "passive"))
      (node (ref "S12_D3") (pin "1") (pinfunction "A_1") (pintype "passive"))
    )
    (net (code "27") (name "Net-(S13_C1-Positive)") (class "Default")
      (node (ref "S13_C1") (pin "1") (pinfunction "Positive_1") (pintype "power_in"))
      (node (ref "S13_C2") (pin "2") (pinfunction "Ground_2") (pintype "power_in"))
      (node (ref "S13_D1") (pin "2") (pinfunction "K_2") (pintype "passive"))
      (node (ref "S13_D2") (pin "1") (pinfunction "A_1") (pintype "passive"))
    )
    (net (code "28") (name "Net-(S13_C2-Positive)") (class "Default")
      (node (ref "S13_C2") (pin "1") (pinfunction "Positive_1") (pintype "power_in"))
      (node (ref "S13_D2") (pin "2") (pinfunction "K_2") (pintype "passive"))
      (node (ref "S13_D3") (pin "1") (pinfunction "A_1") (pintype "passive"))
    )
    (net (code "29") (name "Net-(S14_C1-Positive)") (class "Default")
      (node (ref "S14_C1") (pin "1") (pinfunction "Positive_1") (pintype "power_in"))
      (node (ref "S14_C2") (pin "2") (pinfunction "Ground_2") (pintype "power_in"))
      (node (ref "S14_D1") (pin "2") (pinfunction "K_2") (pintype "passive"))
      (node (ref "S14_D2") (pin "1") (pinfunction "A_1") (pintype "passive"))
    )
    (net (code "30") (name "Net-(S14_C2-Positive)") (class "Default")
      (node (ref "S14_C2") (pin "1") (pinfunction "Positive_1") (pintype "power_in"))
      (node (ref "S14_D2") (pin "2") (pinfunction "K_2") (pintype "passive"))
      (node (ref "S14_D3") (pin "1") (pinfunction "A_1") (pintype "passive"))
    )
    (net (code "31") (name "Net-(S15_C1-Positive)") (class "Default")
      (node (ref "S15_C1") (pin "1") (pinfunction "Positive_1") (pintype "power_in"))
      (node (ref "S15_C2") (pin "2") (pinfunction "Ground_2") (pintype "power_in"))
      (node (ref "S15_D1") (pin "2") (pinfunction "K_2") (pintype "passive"))
      (node (ref "S15_D2") (pin "1") (pinfunction "A_1") (pintype "passive"))
    )
    (net (code "32") (name "Net-(S15_C2-Positive)") (class "Default")
      (node (ref "S15_C2") (pin "1") (pinfunction "Positive_1") (pintype "power_in"))
      (node (ref "S15_D2") (pin "2") (pinfunction "K_2") (pintype "passive"))
      (node (ref "S15_D3") (pin "1") (pinfunction "A_1") (pintype "passive"))
    )
    (net (code "33") (name "Net-(S16_C1-Positive)") (class "Default")
      (node (ref "S16_C1") (pin "1") (pinfunction "Positive_1") (pintype "power_in"))
      (node (ref "S16_C2") (pin "2") (pinfunction "Ground_2") (pintype "power_in"))
      (node (ref "S16_D1") (pin "2") (pinfunction "K_2") (pintype "passive"))
      (node (ref "S16_D2") (pin "1") (pinfunction "A_1") (pintype "passive"))
    )
    (net (code "34") (name "Net-(S16_C2-Positive)") (class "Default")
      (node (ref "S16_C2") (pin "1") (pinfunction "Positive_1") (pintype "power_in"))
      (node (ref "S16_D2") (pin "2") (pinfunction "K_2") (pintype "passive"))
      (node (ref "S16_D3") (pin "1") (pinfunction "A_1") (pintype "passive"))
    )
    (net (code "35") (name "Net-(S17_C1-Positive)") (class "Default")
      (node (ref "S17_C1") (pin "1") (pinfunction "Positive_1") (pintype "power_in"))
      (node (ref "S17_C2") (pin "2") (pinfunction "Ground_2") (pintype "power_in"))
      (node (ref "S17_D1") (pin "2") (pinfunction "K_2") (pintype "passive"))
      (node (ref "S17_D2") (pin "1") (pinfunction "A_1") (pintype "passive"))
    )
    (net (code "36") (name "Net-(S17_C2-Positive)") (class "Default")
      (node (ref "S17_C2") (pin "1") (pinfunction "Positive_1") (pintype "power_in"))
      (node (ref "S17_D2") (pin "2") (pinfunction "K_2") (pintype "passive"))
      (node (ref "S17_D3") (pin "1") (pinfunction "A_1") (pintype "passive"))
    )
    (net (code "37") (name "Net-(S18_C1-Positive)") (class "Default")
      (node (ref "S18_C1") (pin "1") (pinfunction "Positive_1") (pintype "power_in"))
      (node (ref "S18_C2") (pin "2") (pinfunction "Ground_2") (pintype "power_in"))
      (node (ref "S18_D1") (pin "2") (pinfunction "K_2") (pintype "passive"))
      (node (ref "S18_D2") (pin "1") (pinfunction "A_1") (pintype "passive"))
    )
    (net (code "38") (name "Net-(S18_C2-Positive)") (class "Default")
      (node (ref "S18_C2") (pin "1") (pinfunction "Positive_1") (pintype "power_in"))
      (node (ref "S18_D2") (pin "2") (pinfunction "K_2") (pintype "passive"))
      (node (ref "S18_D3") (pin "1") (pinfunction "A_1") (pintype "passive"))
    )
    (net (code "39") (name "Net-(S19_C1-Positive)") (class "Default")
      (node (ref "S19_C1") (pin "1") (pinfunction "Positive_1") (pintype "power_in"))
      (node (ref "S19_C2") (pin "2") (pinfunction "Ground_2") (pintype "power_in"))
      (node (ref "S19_D1") (pin "2") (pinfunction "K_2") (pintype "passive"))
      (node (ref "S19_D2") (pin "1") (pinfunction "A_1") (pintype "passive"))
    )
    (net (code "40") (name "Net-(S19_C2-Positive)") (class "Default")
      (node (ref "S19_C2") (pin "1") (pinfunction "Positive_1") (pintype "power_in"))
      (node (ref "S19_D2") (pin "2") (pinfunction "K_2") (pintype "passive"))
      (node (ref "S19_D3") (pin "1") (pinfunction "A_1") (pintype "passive"))
    )
    (net (code "41") (name "Net-(S20_C1-Positive)") (class "Default")
      (node (ref "S20_C1") (pin "1") (pinfunction "Positive_1") (pintype "power_in"))
      (node (ref "S20_C2") (pin "2") (pinfunction "Ground_2") (pintype "power_in"))
      (node (ref "S20_D1") (pin "2") (pinfunction "K_2") (pintype "passive"))
      (node (ref "S20_D2") (pin "1") (pinfunction "A_1") (pintype "passive"))
    )
    (net (code "42") (name "Net-(S20_C2-Positive)") (class "Default")
      (node (ref "S20_C2") (pin "1") (pinfunction "Positive_1") (pintype "power_in"))
      (node (ref "S20_D2") (pin "2") (pinfunction "K_2") (pintype "passive"))
      (node (ref "S20_D3") (pin "1") (pinfunction "A_1") (pintype "passive"))
    )
    (net (code "43") (name "Net-(S21_C1-Positive)") (class "Default")
      (node (ref "S21_C1") (pin "1") (pinfunction "Positive_1") (pintype "power_in"))
      (node (ref "S21_C2") (pin "2") (pinfunction "Ground_2") (pintype "power_in"))
      (node (ref "S21_D1") (pin "2") (pinfunction "K_2") (pintype "passive"))
      (node (ref "S21_D2") (pin "1") (pinfunction "A_1") (pintype "passive"))
    )
    (net (code "44") (name "Net-(S21_C2-Positive)") (class "Default")
      (node (ref "S21_C2") (pin "1") (pinfunction "Positive_1") (pintype "power_in"))
      (node (ref "S21_D2") (pin "2") (pinfunction "K_2") (pintype "passive"))
      (node (ref "S21_D3") (pin "1") (pinfunction "A_1") (pintype "passive"))
    )
  )
)
